# top.net
KiCad netlist of a schematic drawn in Altium Designer
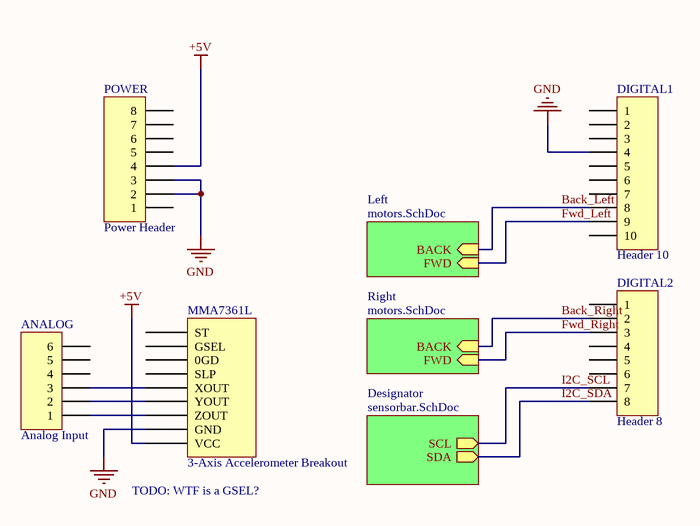
[diagram p0: top.SchDoc]

(export (version "E")
  (design (tool "Eeschema 10.0.6"))
  (components
    (comp (ref "ANALOG")
      (value "Analog Input")
      (footprint "HDR1X6")
      (description "Header, 6-Pin")
      (fields (field (name "PUBLISHER") "Altium Limited"))
      (libsource (lib "Miscellaneous Connectors") (part "Header 6"))
    )
    (comp (ref "DIGITAL1")
      (value "Header 10")
      (footprint "HDR1X10")
      (description "Header, 10-Pin")
      (fields (field (name "PUBLISHER") "Altium Limited"))
      (libsource (lib "Miscellaneous Connectors") (part "Header 10"))
    )
    (comp (ref "DIGITAL2")
      (value "Header 8")
      (footprint "HDR1X8")
      (description "Header, 8-Pin")
      (fields (field (name "PUBLISHER") "Altium Limited"))
      (libsource (lib "Miscellaneous Connectors") (part "Header 8"))
    )
    (comp (ref "MMA7361L")
      (value "3-Axis Accelerometer Breakout")
      (libsource (lib "Schematics") (part "MMA7361L"))
    )
    (comp (ref "POWER")
      (value "Power Header")
      (footprint "HDR1X8")
      (description "Header, 8-Pin")
      (fields (field (name "PUBLISHER") "Altium Limited"))
      (libsource (lib "") (part "Header 8_1"))
    )
  )
  (nets
    (net (code "1") (name "+5V") (class "Default")
      (node (ref "MMA7361L") (pin "VCC") (pinfunction "VCC_VCC") (pintype "passive"))
      (node (ref "POWER") (pin "4") (pinfunction "4_4") (pintype "passive"))
    )
    (net (code "2") (name "/Back_Left") (class "Default")
      (node (ref "DIGITAL1") (pin "8") (pinfunction "8_8") (pintype "passive"))
    )
    (net (code "3") (name "/Back_Right") (class "Default")
      (node (ref "DIGITAL2") (pin "2") (pinfunction "2_2") (pintype "passive"))
    )
    (net (code "4") (name "/Fwd_Left") (class "Default")
      (node (ref "DIGITAL1") (pin "9") (pinfunction "9_9") (pintype "passive"))
    )
    (net (code "5") (name "/Fwd_Right") (class "Default")
      (node (ref "DIGITAL2") (pin "3") (pinfunction "3_3") (pintype "passive"))
    )
    (net (code "6") (name "/I2C_SCL") (class "Default")
      (node (ref "DIGITAL2") (pin "7") (pinfunction "7_7") (pintype "passive"))
    )
    (net (code "7") (name "/I2C_SDA") (class "Default")
      (node (ref "DIGITAL2") (pin "8") (pinfunction "8_8") (pintype "passive"))
    )
    (net (code "8") (name "GND") (class "Default")
      (node (ref "DIGITAL1") (pin "4") (pinfunction "4_4") (pintype "passive"))
      (node (ref "MMA7361L") (pin "GND") (pinfunction "GND_GND") (pintype "passive"))
      (node (ref "POWER") (pin "2") (pinfunction "2_2") (pintype "passive"))
      (node (ref "POWER") (pin "3") (pinfunction "3_3") (pintype "passive"))
    )
    (net (code "9") (name "Net-(ANALOG-Pad1)") (class "Default")
      (node (ref "ANALOG") (pin "1") (pinfunction "1_1") (pintype "passive"))
      (node (ref "MMA7361L") (pin "ZOUT") (pinfunction "ZOUT_ZOUT") (pintype "passive"))
    )
    (net (code "10") (name "Net-(ANALOG-Pad2)") (class "Default")
      (node (ref "ANALOG") (pin "2") (pinfunction "2_2") (pintype "passive"))
      (node (ref "MMA7361L") (pin "YOUT") (pinfunction "YOUT_YOUT") (pintype "passive"))
    )
    (net (code "11") (name "Net-(ANALOG-Pad3)") (class "Default")
      (node (ref "ANALOG") (pin "3") (pinfunction "3_3") (pintype "passive"))
      (node (ref "MMA7361L") (pin "XOUT") (pinfunction "XOUT_XOUT") (pintype "passive"))
    )
    (net (code "12") (name "unconnected-(ANALOG-Pad4)") (class "Default")
      (node (ref "ANALOG") (pin "4") (pinfunction "4_4") (pintype "passive"))
    )
    (net (code "13") (name "unconnected-(ANALOG-Pad5)") (class "Default")
      (node (ref "ANALOG") (pin "5") (pinfunction "5_5") (pintype "passive"))
    )
    (net (code "14") (name "unconnected-(ANALOG-Pad6)") (class "Default")
      (node (ref "ANALOG") (pin "6") (pinfunction "6_6") (pintype "passive"))
    )
    (net (code "15") (name "unconnected-(DIGITAL1-Pad1)") (class "Default")
      (node (ref "DIGITAL1") (pin "1") (pinfunction "1_1") (pintype "passive"))
    )
    (net (code "16") (name "unconnected-(DIGITAL1-Pad2)") (class "Default")
      (node (ref "DIGITAL1") (pin "2") (pinfunction "2_2") (pintype "passive"))
    )
    (net (code "17") (name "unconnected-(DIGITAL1-Pad3)") (class "Default")
      (node (ref "DIGITAL1") (pin "3") (pinfunction "3_3") (pintype "passive"))
    )
    (net (code "18") (name "unconnected-(DIGITAL1-Pad5)") (class "Default")
      (node (ref "DIGITAL1") (pin "5") (pinfunction "5_5") (pintype "passive"))
    )
    (net (code "19") (name "unconnected-(DIGITAL1-Pad6)") (class "Default")
      (node (ref "DIGITAL1") (pin "6") (pinfunction "6_6") (pintype "passive"))
    )
    (net (code "20") (name "unconnected-(DIGITAL1-Pad7)") (class "Default")
      (node (ref "DIGITAL1") (pin "7") (pinfunction "7_7") (pintype "passive"))
    )
    (net (code "21") (name "unconnected-(DIGITAL1-Pad10)") (class "Default")
      (node (ref "DIGITAL1") (pin "10") (pinfunction "10_10") (pintype "passive"))
    )
    (net (code "22") (name "unconnected-(DIGITAL2-Pad1)") (class "Default")
      (node (ref "DIGITAL2") (pin "1") (pinfunction "1_1") (pintype "passive"))
    )
    (net (code "23") (name "unconnected-(DIGITAL2-Pad4)") (class "Default")
      (node (ref "DIGITAL2") (pin "4") (pinfunction "4_4") (pintype "passive"))
    )
    (net (code "24") (name "unconnected-(DIGITAL2-Pad5)") (class "Default")
      (node (ref "DIGITAL2") (pin "5") (pinfunction "5_5") (pintype "passive"))
    )
    (net (code "25") (name "unconnected-(DIGITAL2-Pad6)") (class "Default")
      (node (ref "DIGITAL2") (pin "6") (pinfunction "6_6") (pintype "passive"))
    )
    (net (code "26") (name "unconnected-(MMA7361L-Pad0GD)") (class "Default")
      (node (ref "MMA7361L") (pin "0GD") (pinfunction "0GD_0GD") (pintype "passive"))
    )
    (net (code "27") (name "unconnected-(MMA7361L-PadGSEL)") (class "Default")
      (node (ref "MMA7361L") (pin "GSEL") (pinfunction "GSEL_GSEL") (pintype "passive"))
    )
    (net (code "28") (name "unconnected-(MMA7361L-PadSLP)") (class "Default")
      (node (ref "MMA7361L") (pin "SLP") (pinfunction "SLP_SLP") (pintype "passive"))
    )
    (net (code "29") (name "unconnected-(MMA7361L-PadST)") (class "Default")
      (node (ref "MMA7361L") (pin "ST") (pinfunction "ST_ST") (pintype "passive"))
    )
    (net (code "30") (name "unconnected-(POWER-Pad1)") (class "Default")
      (node (ref "POWER") (pin "1") (pinfunction "1_1") (pintype "passive"))
    )
    (net (code "31") (name "unconnected-(POWER-Pad5)") (class "Default")
      (node (ref "POWER") (pin "5") (pinfunction "5_5") (pintype "passive"))
    )
    (net (code "32") (name "unconnected-(POWER-Pad6)") (class "Default")
      (node (ref "POWER") (pin "6") (pinfunction "6_6") (pintype "passive"))
    )
    (net (code "33") (name "unconnected-(POWER-Pad7)") (class "Default")
      (node (ref "POWER") (pin "7") (pinfunction "7_7") (pintype "passive"))
    )
    (net (code "34") (name "unconnected-(POWER-Pad8)") (class "Default")
      (node (ref "POWER") (pin "8") (pinfunction "8_8") (pintype "passive"))
    )
  )
)
